# Safety_2019_V_3_0_Connector_Filter.net
KiCad netlist of a schematic drawn in Altium Designer
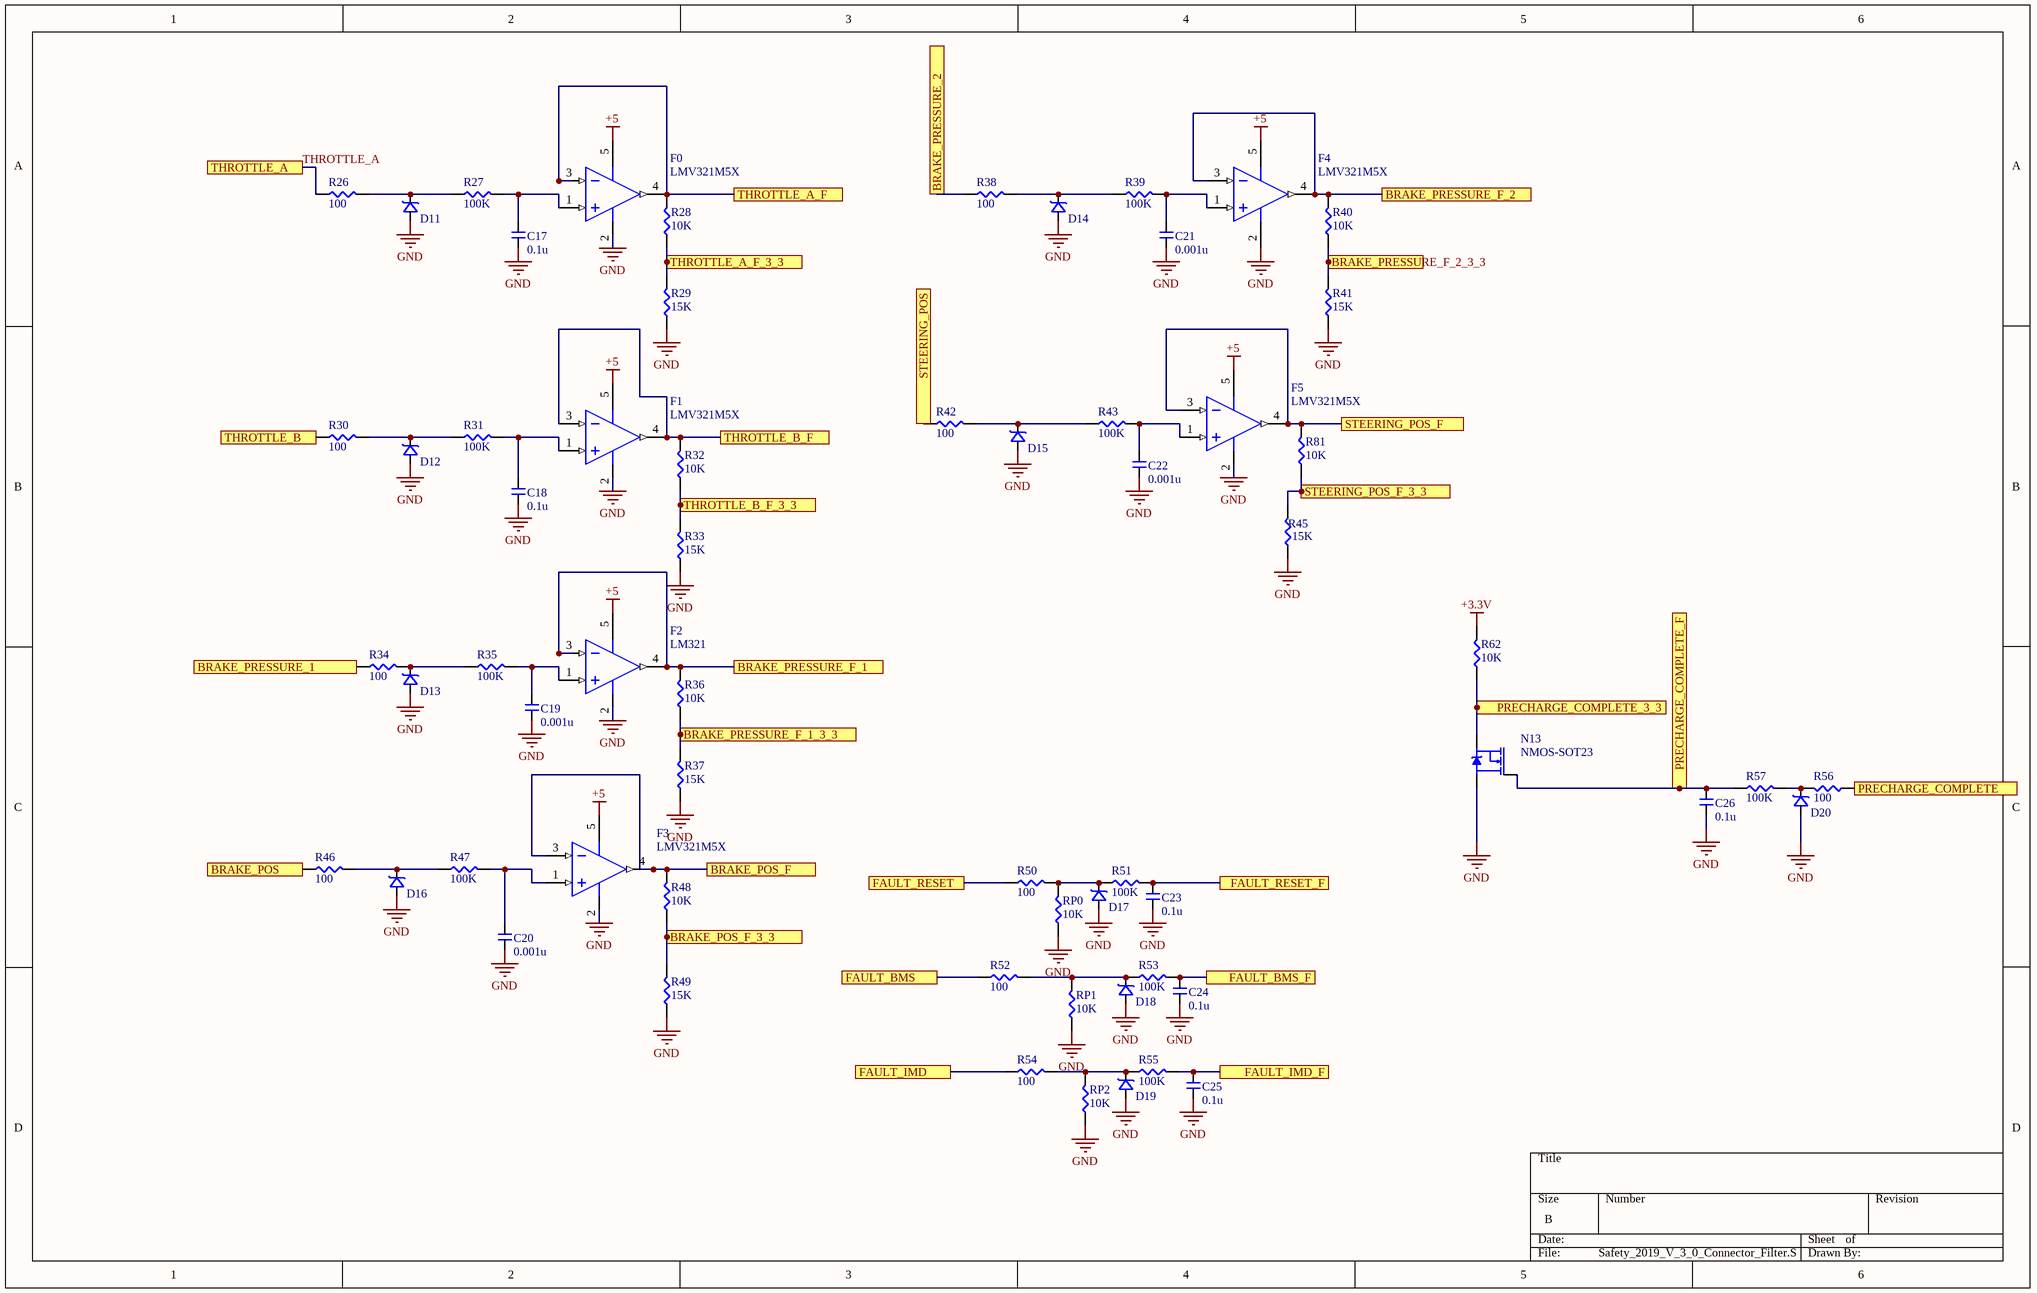
[diagram p0: Safety_2019_V_3_0_Connector_Filter.SchDoc]

(export (version "E")
  (design (tool "Eeschema 10.0.6"))
  (components
    (comp (ref "C17")
      (value "0.1u")
      (footprint "CAP-0603")
      (libsource (lib "ife19_Elec_Library") (part "CAP-0603"))
    )
    (comp (ref "C18")
      (value "0.1u")
      (footprint "CAP-0603")
      (libsource (lib "ife19_Elec_Library") (part "CAP-0603"))
    )
    (comp (ref "C19")
      (value "0.001u")
      (footprint "CAP-0603")
      (libsource (lib "ife19_Elec_Library") (part "CAP-0603"))
    )
    (comp (ref "C20")
      (value "0.001u")
      (footprint "CAP-0603")
      (libsource (lib "ife19_Elec_Library") (part "CAP-0603"))
    )
    (comp (ref "C21")
      (value "0.001u")
      (footprint "CAP-0603")
      (libsource (lib "ife19_Elec_Library") (part "CAP-0603"))
    )
    (comp (ref "C22")
      (value "0.001u")
      (footprint "CAP-0603")
      (libsource (lib "ife19_Elec_Library") (part "CAP-0603"))
    )
    (comp (ref "C23")
      (value "0.1u")
      (footprint "CAP-0603")
      (libsource (lib "ife19_Elec_Library") (part "CAP-0603"))
    )
    (comp (ref "C24")
      (value "0.1u")
      (footprint "CAP-0603")
      (libsource (lib "ife19_Elec_Library") (part "CAP-0603"))
    )
    (comp (ref "C25")
      (value "0.1u")
      (footprint "CAP-0603")
      (libsource (lib "ife19_Elec_Library") (part "CAP-0603"))
    )
    (comp (ref "C26")
      (value "0.1u")
      (footprint "CAP-0603")
      (libsource (lib "ife19_Elec_Library") (part "CAP-0603"))
    )
    (comp (ref "D11") (value "?") (footprint "SMB") (libsource (lib "ife19_Elec_Library") (part "DIODE-SMB")))
    (comp (ref "D12") (value "?") (footprint "SMB") (libsource (lib "ife19_Elec_Library") (part "DIODE-SMB")))
    (comp (ref "D13") (value "?") (footprint "SMB") (libsource (lib "ife19_Elec_Library") (part "DIODE-SMB")))
    (comp (ref "D14") (value "?") (footprint "SMB") (libsource (lib "ife19_Elec_Library") (part "DIODE-SMB")))
    (comp (ref "D15") (value "?") (footprint "SMB") (libsource (lib "ife19_Elec_Library") (part "DIODE-SMB")))
    (comp (ref "D16") (value "?") (footprint "SMB") (libsource (lib "ife19_Elec_Library") (part "DIODE-SMB")))
    (comp (ref "D17") (value "?") (footprint "SMB") (libsource (lib "ife19_Elec_Library") (part "DIODE-SMB")))
    (comp (ref "D18") (value "?") (footprint "SMB") (libsource (lib "ife19_Elec_Library") (part "DIODE-SMB")))
    (comp (ref "D19") (value "?") (footprint "SMB") (libsource (lib "ife19_Elec_Library") (part "DIODE-SMB")))
    (comp (ref "D20") (value "?") (footprint "SMB") (libsource (lib "ife19_Elec_Library") (part "DIODE-SMB")))
    (comp (ref "F0")
      (value "LMV321M5X")
      (footprint "MF05A_N")
      (description "General Purpose, Low Voltage, Rail-to-Rail Output Operational Amplifiers, 5-pin SOT-23")
      (fields (field (name "MANUFACTURER") "National Semiconductor"))
      (libsource (lib "Altium Content Vault") (part "AMP-OPA-LMV551-5"))
    )
    (comp (ref "F1")
      (value "LMV321M5X")
      (footprint "MF05A_N")
      (description "General Purpose, Low Voltage, Rail-to-Rail Output Operational Amplifiers, 5-pin SOT-23")
      (fields (field (name "MANUFACTURER") "National Semiconductor"))
      (libsource (lib "Altium Content Vault") (part "AMP-OPA-LMV551-5"))
    )
    (comp (ref "F2")
      (value "LM321")
      (footprint "MF05A_N")
      (description "General Purpose, Low Voltage, Rail-to-Rail Output Operational Amplifiers, 5-pin SOT-23")
      (fields (field (name "MANUFACTURER") "National Semiconductor"))
      (libsource (lib "Altium Content Vault") (part "AMP-OPA-LMV551-5"))
    )
    (comp (ref "F3")
      (value "LMV321M5X")
      (footprint "MF05A_N")
      (description "General Purpose, Low Voltage, Rail-to-Rail Output Operational Amplifiers, 5-pin SOT-23")
      (fields (field (name "MANUFACTURER") "National Semiconductor"))
      (libsource (lib "Altium Content Vault") (part "AMP-OPA-LMV551-5"))
    )
    (comp (ref "F4")
      (value "LMV321M5X")
      (footprint "MF05A_N")
      (description "General Purpose, Low Voltage, Rail-to-Rail Output Operational Amplifiers, 5-pin SOT-23")
      (fields (field (name "MANUFACTURER") "National Semiconductor"))
      (libsource (lib "Altium Content Vault") (part "AMP-OPA-LMV551-5"))
    )
    (comp (ref "F5")
      (value "LMV321M5X")
      (footprint "MF05A_N")
      (description "General Purpose, Low Voltage, Rail-to-Rail Output Operational Amplifiers, 5-pin SOT-23")
      (fields (field (name "MANUFACTURER") "National Semiconductor"))
      (libsource (lib "Altium Content Vault") (part "AMP-OPA-LMV551-5"))
    )
    (comp (ref "N13")
      (value "NMOS-SOT23")
      (footprint "SOT23")
      (libsource (lib "ife19_Elec_Library") (part "NMOS-SOT23"))
    )
    (comp (ref "R26")
      (value "100")
      (footprint "RES-0603")
      (libsource (lib "ife19_Elec_Library") (part "RES-0603"))
    )
    (comp (ref "R27")
      (value "100K")
      (footprint "RES-0603")
      (libsource (lib "ife19_Elec_Library") (part "RES-0603"))
    )
    (comp (ref "R28")
      (value "10K")
      (footprint "RES-0603")
      (libsource (lib "ife19_Elec_Library") (part "RES-0603"))
    )
    (comp (ref "R29")
      (value "15K")
      (footprint "RES-0603")
      (libsource (lib "ife19_Elec_Library") (part "RES-0603"))
    )
    (comp (ref "R30")
      (value "100")
      (footprint "RES-0603")
      (libsource (lib "ife19_Elec_Library") (part "RES-0603"))
    )
    (comp (ref "R31")
      (value "100K")
      (footprint "RES-0603")
      (libsource (lib "ife19_Elec_Library") (part "RES-0603"))
    )
    (comp (ref "R32")
      (value "10K")
      (footprint "RES-0603")
      (libsource (lib "ife19_Elec_Library") (part "RES-0603"))
    )
    (comp (ref "R33")
      (value "15K")
      (footprint "RES-0603")
      (libsource (lib "ife19_Elec_Library") (part "RES-0603"))
    )
    (comp (ref "R34")
      (value "100")
      (footprint "RES-0603")
      (libsource (lib "ife19_Elec_Library") (part "RES-0603"))
    )
    (comp (ref "R35")
      (value "100K")
      (footprint "RES-0603")
      (libsource (lib "ife19_Elec_Library") (part "RES-0603"))
    )
    (comp (ref "R36")
      (value "10K")
      (footprint "RES-0603")
      (libsource (lib "ife19_Elec_Library") (part "RES-0603"))
    )
    (comp (ref "R37")
      (value "15K")
      (footprint "RES-0603")
      (libsource (lib "ife19_Elec_Library") (part "RES-0603"))
    )
    (comp (ref "R38")
      (value "100")
      (footprint "RES-0603")
      (libsource (lib "ife19_Elec_Library") (part "RES-0603"))
    )
    (comp (ref "R39")
      (value "100K")
      (footprint "RES-0603")
      (libsource (lib "ife19_Elec_Library") (part "RES-0603"))
    )
    (comp (ref "R40")
      (value "10K")
      (footprint "RES-0603")
      (libsource (lib "ife19_Elec_Library") (part "RES-0603"))
    )
    (comp (ref "R41")
      (value "15K")
      (footprint "RES-0603")
      (libsource (lib "ife19_Elec_Library") (part "RES-0603"))
    )
    (comp (ref "R42")
      (value "100")
      (footprint "RES-0603")
      (libsource (lib "ife19_Elec_Library") (part "RES-0603"))
    )
    (comp (ref "R43")
      (value "100K")
      (footprint "RES-0603")
      (libsource (lib "ife19_Elec_Library") (part "RES-0603"))
    )
    (comp (ref "R45")
      (value "15K")
      (footprint "RES-0603")
      (libsource (lib "ife19_Elec_Library") (part "RES-0603"))
    )
    (comp (ref "R46")
      (value "100")
      (footprint "RES-0603")
      (libsource (lib "ife19_Elec_Library") (part "RES-0603"))
    )
    (comp (ref "R47")
      (value "100K")
      (footprint "RES-0603")
      (libsource (lib "ife19_Elec_Library") (part "RES-0603"))
    )
    (comp (ref "R48")
      (value "10K")
      (footprint "RES-0603")
      (libsource (lib "ife19_Elec_Library") (part "RES-0603"))
    )
    (comp (ref "R49")
      (value "15K")
      (footprint "RES-0603")
      (libsource (lib "ife19_Elec_Library") (part "RES-0603"))
    )
    (comp (ref "R50")
      (value "100")
      (footprint "RES-0603")
      (libsource (lib "ife19_Elec_Library") (part "RES-0603"))
    )
    (comp (ref "R51")
      (value "100K")
      (footprint "RES-0603")
      (libsource (lib "ife19_Elec_Library") (part "RES-0603"))
    )
    (comp (ref "R52")
      (value "100")
      (footprint "RES-0603")
      (libsource (lib "ife19_Elec_Library") (part "RES-0603"))
    )
    (comp (ref "R53")
      (value "100K")
      (footprint "RES-0603")
      (libsource (lib "ife19_Elec_Library") (part "RES-0603"))
    )
    (comp (ref "R54")
      (value "100")
      (footprint "RES-0603")
      (libsource (lib "ife19_Elec_Library") (part "RES-0603"))
    )
    (comp (ref "R55")
      (value "100K")
      (footprint "RES-0603")
      (libsource (lib "ife19_Elec_Library") (part "RES-0603"))
    )
    (comp (ref "R56")
      (value "100")
      (footprint "RES-0603")
      (libsource (lib "ife19_Elec_Library") (part "RES-0603"))
    )
    (comp (ref "R57")
      (value "100K")
      (footprint "RES-0603")
      (libsource (lib "ife19_Elec_Library") (part "RES-0603"))
    )
    (comp (ref "R62")
      (value "10K")
      (footprint "RES-0603")
      (libsource (lib "ife19_Elec_Library") (part "RES-0603"))
    )
    (comp (ref "R81")
      (value "10K")
      (footprint "RES-0603")
      (libsource (lib "ife19_Elec_Library") (part "RES-0603"))
    )
    (comp (ref "RP0")
      (value "10K")
      (footprint "RES-0603")
      (libsource (lib "ife19_Elec_Library") (part "RES-0603"))
    )
    (comp (ref "RP1")
      (value "10K")
      (footprint "RES-0603")
      (libsource (lib "ife19_Elec_Library") (part "RES-0603"))
    )
    (comp (ref "RP2")
      (value "10K")
      (footprint "RES-0603")
      (libsource (lib "ife19_Elec_Library") (part "RES-0603"))
    )
  )
  (nets
    (net (code "1") (name "+3.3V") (class "Default")
      (node (ref "R62") (pin "2") (pinfunction "2_2") (pintype "passive"))
    )
    (net (code "2") (name "+5") (class "Default")
      (node (ref "F0") (pin "5") (pinfunction "V+_5") (pintype "power_in"))
      (node (ref "F1") (pin "5") (pinfunction "V+_5") (pintype "power_in"))
      (node (ref "F2") (pin "5") (pinfunction "V+_5") (pintype "power_in"))
      (node (ref "F3") (pin "5") (pinfunction "V+_5") (pintype "power_in"))
      (node (ref "F4") (pin "5") (pinfunction "V+_5") (pintype "power_in"))
      (node (ref "F5") (pin "5") (pinfunction "V+_5") (pintype "power_in"))
    )
    (net (code "3") (name "/BRAKE_POS") (class "Default")
      (node (ref "R46") (pin "1") (pinfunction "1_1") (pintype "passive"))
    )
    (net (code "4") (name "/BRAKE_POS_F") (class "Default")
      (node (ref "F3") (pin "3") (pinfunction "IN-_3") (pintype "input"))
      (node (ref "F3") (pin "4") (pinfunction "OUT_4") (pintype "output"))
      (node (ref "R48") (pin "2") (pinfunction "2_2") (pintype "passive"))
    )
    (net (code "5") (name "/BRAKE_POS_F_3_3") (class "Default")
      (node (ref "R48") (pin "1") (pinfunction "1_1") (pintype "passive"))
      (node (ref "R49") (pin "2") (pinfunction "2_2") (pintype "passive"))
    )
    (net (code "6") (name "/BRAKE_PRESSURE_1") (class "Default")
      (node (ref "R34") (pin "1") (pinfunction "1_1") (pintype "passive"))
    )
    (net (code "7") (name "/BRAKE_PRESSURE_2") (class "Default")
      (node (ref "R38") (pin "1") (pinfunction "1_1") (pintype "passive"))
    )
    (net (code "8") (name "/BRAKE_PRESSURE_F_1") (class "Default")
      (node (ref "F2") (pin "3") (pinfunction "IN-_3") (pintype "input"))
      (node (ref "F2") (pin "4") (pinfunction "OUT_4") (pintype "output"))
      (node (ref "R36") (pin "2") (pinfunction "2_2") (pintype "passive"))
    )
    (net (code "9") (name "/BRAKE_PRESSURE_F_1_3_3") (class "Default")
      (node (ref "R36") (pin "1") (pinfunction "1_1") (pintype "passive"))
      (node (ref "R37") (pin "2") (pinfunction "2_2") (pintype "passive"))
    )
    (net (code "10") (name "/BRAKE_PRESSURE_F_2") (class "Default")
      (node (ref "F4") (pin "3") (pinfunction "IN-_3") (pintype "input"))
      (node (ref "F4") (pin "4") (pinfunction "OUT_4") (pintype "output"))
      (node (ref "R40") (pin "2") (pinfunction "2_2") (pintype "passive"))
    )
    (net (code "11") (name "/BRAKE_PRESSURE_F_2_3_3") (class "Default")
      (node (ref "R40") (pin "1") (pinfunction "1_1") (pintype "passive"))
      (node (ref "R41") (pin "2") (pinfunction "2_2") (pintype "passive"))
    )
    (net (code "12") (name "/FAULT_BMS") (class "Default")
      (node (ref "R52") (pin "1") (pinfunction "1_1") (pintype "passive"))
    )
    (net (code "13") (name "/FAULT_BMS_F") (class "Default")
      (node (ref "C24") (pin "2") (pinfunction "2_2") (pintype "passive"))
      (node (ref "R53") (pin "2") (pinfunction "2_2") (pintype "passive"))
    )
    (net (code "14") (name "/FAULT_IMD") (class "Default")
      (node (ref "R54") (pin "1") (pinfunction "1_1") (pintype "passive"))
    )
    (net (code "15") (name "/FAULT_IMD_F") (class "Default")
      (node (ref "C25") (pin "2") (pinfunction "2_2") (pintype "passive"))
      (node (ref "R55") (pin "2") (pinfunction "2_2") (pintype "passive"))
    )
    (net (code "16") (name "/FAULT_RESET") (class "Default")
      (node (ref "R50") (pin "1") (pinfunction "1_1") (pintype "passive"))
    )
    (net (code "17") (name "/FAULT_RESET_F") (class "Default")
      (node (ref "C23") (pin "2") (pinfunction "2_2") (pintype "passive"))
      (node (ref "R51") (pin "2") (pinfunction "2_2") (pintype "passive"))
    )
    (net (code "18") (name "/PRECHARGE_COMPLETE") (class "Default")
      (node (ref "R56") (pin "1") (pinfunction "1_1") (pintype "passive"))
    )
    (net (code "19") (name "/PRECHARGE_COMPLETE_3_3") (class "Default")
      (node (ref "N13") (pin "3") (pinfunction "D_3") (pintype "passive"))
      (node (ref "R62") (pin "1") (pinfunction "1_1") (pintype "passive"))
    )
    (net (code "20") (name "/PRECHARGE_COMPLETE_F") (class "Default")
      (node (ref "C26") (pin "2") (pinfunction "2_2") (pintype "passive"))
      (node (ref "N13") (pin "1") (pinfunction "G_1") (pintype "passive"))
      (node (ref "R57") (pin "1") (pinfunction "1_1") (pintype "passive"))
    )
    (net (code "21") (name "/STEERING_POS") (class "Default")
      (node (ref "R42") (pin "1") (pinfunction "1_1") (pintype "passive"))
    )
    (net (code "22") (name "/STEERING_POS_F") (class "Default")
      (node (ref "F5") (pin "3") (pinfunction "IN-_3") (pintype "input"))
      (node (ref "F5") (pin "4") (pinfunction "OUT_4") (pintype "output"))
      (node (ref "R81") (pin "2") (pinfunction "2_2") (pintype "passive"))
    )
    (net (code "23") (name "/STEERING_POS_F_3_3") (class "Default")
      (node (ref "R45") (pin "2") (pinfunction "2_2") (pintype "passive"))
      (node (ref "R81") (pin "1") (pinfunction "1_1") (pintype "passive"))
    )
    (net (code "24") (name "/THROTTLE_A") (class "Default")
      (node (ref "R26") (pin "1") (pinfunction "1_1") (pintype "passive"))
    )
    (net (code "25") (name "/THROTTLE_A_F") (class "Default")
      (node (ref "F0") (pin "3") (pinfunction "IN-_3") (pintype "input"))
      (node (ref "F0") (pin "4") (pinfunction "OUT_4") (pintype "output"))
      (node (ref "R28") (pin "2") (pinfunction "2_2") (pintype "passive"))
    )
    (net (code "26") (name "/THROTTLE_A_F_3_3") (class "Default")
      (node (ref "R28") (pin "1") (pinfunction "1_1") (pintype "passive"))
      (node (ref "R29") (pin "2") (pinfunction "2_2") (pintype "passive"))
    )
    (net (code "27") (name "/THROTTLE_B") (class "Default")
      (node (ref "R30") (pin "1") (pinfunction "1_1") (pintype "passive"))
    )
    (net (code "28") (name "/THROTTLE_B_F") (class "Default")
      (node (ref "F1") (pin "3") (pinfunction "IN-_3") (pintype "input"))
      (node (ref "F1") (pin "4") (pinfunction "OUT_4") (pintype "output"))
      (node (ref "R32") (pin "2") (pinfunction "2_2") (pintype "passive"))
    )
    (net (code "29") (name "/THROTTLE_B_F_3_3") (class "Default")
      (node (ref "R32") (pin "1") (pinfunction "1_1") (pintype "passive"))
      (node (ref "R33") (pin "2") (pinfunction "2_2") (pintype "passive"))
    )
    (net (code "30") (name "GND") (class "Default")
      (node (ref "C17") (pin "2") (pinfunction "2_2") (pintype "passive"))
      (node (ref "C18") (pin "2") (pinfunction "2_2") (pintype "passive"))
      (node (ref "C19") (pin "2") (pinfunction "2_2") (pintype "passive"))
      (node (ref "C20") (pin "2") (pinfunction "2_2") (pintype "passive"))
      (node (ref "C21") (pin "2") (pinfunction "2_2") (pintype "passive"))
      (node (ref "C22") (pin "2") (pinfunction "2_2") (pintype "passive"))
      (node (ref "C23") (pin "1") (pinfunction "1_1") (pintype "passive"))
      (node (ref "C24") (pin "1") (pinfunction "1_1") (pintype "passive"))
      (node (ref "C25") (pin "1") (pinfunction "1_1") (pintype "passive"))
      (node (ref "C26") (pin "1") (pinfunction "1_1") (pintype "passive"))
      (node (ref "D11") (pin "A") (pinfunction "A_A") (pintype "passive"))
      (node (ref "D12") (pin "A") (pinfunction "A_A") (pintype "passive"))
      (node (ref "D13") (pin "A") (pinfunction "A_A") (pintype "passive"))
      (node (ref "D14") (pin "A") (pinfunction "A_A") (pintype "passive"))
      (node (ref "D15") (pin "A") (pinfunction "A_A") (pintype "passive"))
      (node (ref "D16") (pin "A") (pinfunction "A_A") (pintype "passive"))
      (node (ref "D17") (pin "A") (pinfunction "A_A") (pintype "passive"))
      (node (ref "D18") (pin "A") (pinfunction "A_A") (pintype "passive"))
      (node (ref "D19") (pin "A") (pinfunction "A_A") (pintype "passive"))
      (node (ref "D20") (pin "A") (pinfunction "A_A") (pintype "passive"))
      (node (ref "F0") (pin "2") (pinfunction "V-_2") (pintype "power_in"))
      (node (ref "F1") (pin "2") (pinfunction "V-_2") (pintype "power_in"))
      (node (ref "F2") (pin "2") (pinfunction "V-_2") (pintype "power_in"))
      (node (ref "F3") (pin "2") (pinfunction "V-_2") (pintype "power_in"))
      (node (ref "F4") (pin "2") (pinfunction "V-_2") (pintype "power_in"))
      (node (ref "F5") (pin "2") (pinfunction "V-_2") (pintype "power_in"))
      (node (ref "N13") (pin "2") (pinfunction "S_2") (pintype "passive"))
      (node (ref "R29") (pin "1") (pinfunction "1_1") (pintype "passive"))
      (node (ref "R33") (pin "1") (pinfunction "1_1") (pintype "passive"))
      (node (ref "R37") (pin "1") (pinfunction "1_1") (pintype "passive"))
      (node (ref "R41") (pin "1") (pinfunction "1_1") (pintype "passive"))
      (node (ref "R45") (pin "1") (pinfunction "1_1") (pintype "passive"))
      (node (ref "R49") (pin "1") (pinfunction "1_1") (pintype "passive"))
      (node (ref "RP0") (pin "1") (pinfunction "1_1") (pintype "passive"))
      (node (ref "RP1") (pin "1") (pinfunction "1_1") (pintype "passive"))
      (node (ref "RP2") (pin "1") (pinfunction "1_1") (pintype "passive"))
    )
    (net (code "31") (name "Net-(D11-PadK)") (class "Default")
      (node (ref "D11") (pin "K") (pinfunction "K_K") (pintype "passive"))
      (node (ref "R26") (pin "2") (pinfunction "2_2") (pintype "passive"))
      (node (ref "R27") (pin "1") (pinfunction "1_1") (pintype "passive"))
    )
    (net (code "32") (name "Net-(D12-PadK)") (class "Default")
      (node (ref "D12") (pin "K") (pinfunction "K_K") (pintype "passive"))
      (node (ref "R30") (pin "2") (pinfunction "2_2") (pintype "passive"))
      (node (ref "R31") (pin "1") (pinfunction "1_1") (pintype "passive"))
    )
    (net (code "33") (name "Net-(D13-PadK)") (class "Default")
      (node (ref "D13") (pin "K") (pinfunction "K_K") (pintype "passive"))
      (node (ref "R34") (pin "2") (pinfunction "2_2") (pintype "passive"))
      (node (ref "R35") (pin "1") (pinfunction "1_1") (pintype "passive"))
    )
    (net (code "34") (name "Net-(D14-PadK)") (class "Default")
      (node (ref "D14") (pin "K") (pinfunction "K_K") (pintype "passive"))
      (node (ref "R38") (pin "2") (pinfunction "2_2") (pintype "passive"))
      (node (ref "R39") (pin "1") (pinfunction "1_1") (pintype "passive"))
    )
    (net (code "35") (name "Net-(D15-PadK)") (class "Default")
      (node (ref "D15") (pin "K") (pinfunction "K_K") (pintype "passive"))
      (node (ref "R42") (pin "2") (pinfunction "2_2") (pintype "passive"))
      (node (ref "R43") (pin "1") (pinfunction "1_1") (pintype "passive"))
    )
    (net (code "36") (name "Net-(D16-PadK)") (class "Default")
      (node (ref "D16") (pin "K") (pinfunction "K_K") (pintype "passive"))
      (node (ref "R46") (pin "2") (pinfunction "2_2") (pintype "passive"))
      (node (ref "R47") (pin "1") (pinfunction "1_1") (pintype "passive"))
    )
    (net (code "37") (name "Net-(D17-PadK)") (class "Default")
      (node (ref "D17") (pin "K") (pinfunction "K_K") (pintype "passive"))
      (node (ref "R50") (pin "2") (pinfunction "2_2") (pintype "passive"))
      (node (ref "R51") (pin "1") (pinfunction "1_1") (pintype "passive"))
      (node (ref "RP0") (pin "2") (pinfunction "2_2") (pintype "passive"))
    )
    (net (code "38") (name "Net-(D18-PadK)") (class "Default")
      (node (ref "D18") (pin "K") (pinfunction "K_K") (pintype "passive"))
      (node (ref "R52") (pin "2") (pinfunction "2_2") (pintype "passive"))
      (node (ref "R53") (pin "1") (pinfunction "1_1") (pintype "passive"))
      (node (ref "RP1") (pin "2") (pinfunction "2_2") (pintype "passive"))
    )
    (net (code "39") (name "Net-(D19-PadK)") (class "Default")
      (node (ref "D19") (pin "K") (pinfunction "K_K") (pintype "passive"))
      (node (ref "R54") (pin "2") (pinfunction "2_2") (pintype "passive"))
      (node (ref "R55") (pin "1") (pinfunction "1_1") (pintype "passive"))
      (node (ref "RP2") (pin "2") (pinfunction "2_2") (pintype "passive"))
    )
    (net (code "40") (name "Net-(D20-PadK)") (class "Default")
      (node (ref "D20") (pin "K") (pinfunction "K_K") (pintype "passive"))
      (node (ref "R56") (pin "2") (pinfunction "2_2") (pintype "passive"))
      (node (ref "R57") (pin "2") (pinfunction "2_2") (pintype "passive"))
    )
    (net (code "41") (name "Net-(F0-IN+)") (class "Default")
      (node (ref "C17") (pin "1") (pinfunction "1_1") (pintype "passive"))
      (node (ref "F0") (pin "1") (pinfunction "IN+_1") (pintype "input"))
      (node (ref "R27") (pin "2") (pinfunction "2_2") (pintype "passive"))
    )
    (net (code "42") (name "Net-(F1-IN+)") (class "Default")
      (node (ref "C18") (pin "1") (pinfunction "1_1") (pintype "passive"))
      (node (ref "F1") (pin "1") (pinfunction "IN+_1") (pintype "input"))
      (node (ref "R31") (pin "2") (pinfunction "2_2") (pintype "passive"))
    )
    (net (code "43") (name "Net-(F2-IN+)") (class "Default")
      (node (ref "C19") (pin "1") (pinfunction "1_1") (pintype "passive"))
      (node (ref "F2") (pin "1") (pinfunction "IN+_1") (pintype "input"))
      (node (ref "R35") (pin "2") (pinfunction "2_2") (pintype "passive"))
    )
    (net (code "44") (name "Net-(F3-IN+)") (class "Default")
      (node (ref "C20") (pin "1") (pinfunction "1_1") (pintype "passive"))
      (node (ref "F3") (pin "1") (pinfunction "IN+_1") (pintype "input"))
      (node (ref "R47") (pin "2") (pinfunction "2_2") (pintype "passive"))
    )
    (net (code "45") (name "Net-(F4-IN+)") (class "Default")
      (node (ref "C21") (pin "1") (pinfunction "1_1") (pintype "passive"))
      (node (ref "F4") (pin "1") (pinfunction "IN+_1") (pintype "input"))
      (node (ref "R39") (pin "2") (pinfunction "2_2") (pintype "passive"))
    )
    (net (code "46") (name "Net-(F5-IN+)") (class "Default")
      (node (ref "C22") (pin "1") (pinfunction "1_1") (pintype "passive"))
      (node (ref "F5") (pin "1") (pinfunction "IN+_1") (pintype "input"))
      (node (ref "R43") (pin "2") (pinfunction "2_2") (pintype "passive"))
    )
  )
)
